# ERN_Main_4.net
KiCad netlist of a schematic drawn in Altium Designer
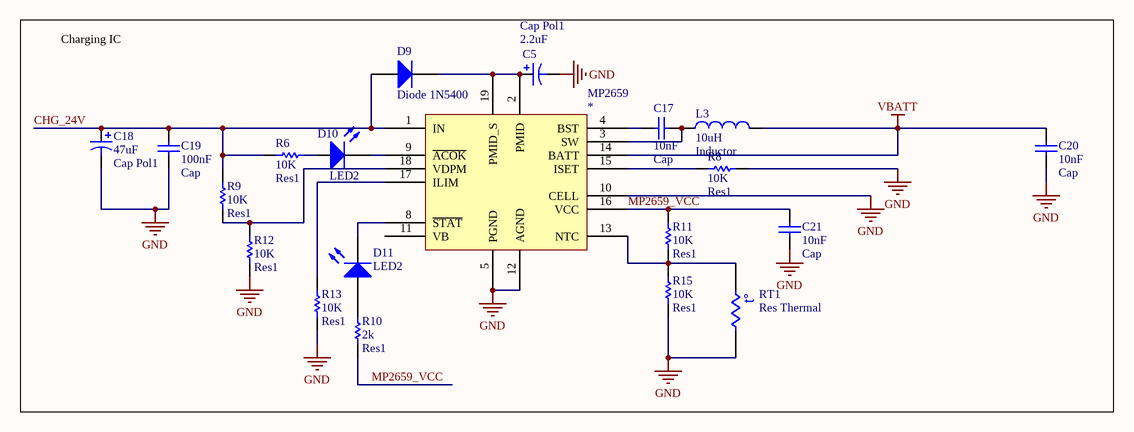
[diagram p0: ERN_Main_4.SchDoc]

(export (version "E")
  (design (tool "Eeschema 10.0.6"))
  (components
    (comp (ref "*")
      (value "MP2659")
      (description "3S-6S Standalone Switching Charger")
      (libsource (lib "ERN") (part "MP2659"))
    )
    (comp (ref "C5")
      (value "Cap Pol1")
      (footprint "RB7.6-15")
      (description "Polarized Capacitor (Radial)")
      (fields (field (name "ALTIUM_VALUE") "2.2uF") (field (name "PUBLISHER") "Altium Limited"))
      (libsource (lib "Miscellaneous Devices") (part "Cap Pol1"))
    )
    (comp (ref "C17")
      (value "Cap")
      (footprint "RAD-0.3")
      (description "Capacitor")
      (fields (field (name "ALTIUM_VALUE") "10nF") (field (name "PUBLISHER") "Altium Limited"))
      (libsource (lib "Miscellaneous Devices") (part "Cap"))
    )
    (comp (ref "C18")
      (value "Cap Pol1")
      (footprint "RB7.6-15")
      (description "Polarized Capacitor (Radial)")
      (fields (field (name "ALTIUM_VALUE") "47uF") (field (name "PUBLISHER") "Altium Limited"))
      (libsource (lib "Miscellaneous Devices") (part "Cap Pol1"))
    )
    (comp (ref "C19")
      (value "Cap")
      (footprint "RAD-0.3")
      (description "Capacitor")
      (fields (field (name "ALTIUM_VALUE") "100nF") (field (name "PUBLISHER") "Altium Limited"))
      (libsource (lib "Miscellaneous Devices") (part "Cap"))
    )
    (comp (ref "C20")
      (value "Cap")
      (footprint "RAD-0.3")
      (description "Capacitor")
      (fields (field (name "ALTIUM_VALUE") "10nF") (field (name "PUBLISHER") "Altium Limited"))
      (libsource (lib "Miscellaneous Devices") (part "Cap"))
    )
    (comp (ref "C21")
      (value "Cap")
      (footprint "RAD-0.3")
      (description "Capacitor")
      (fields (field (name "ALTIUM_VALUE") "10nF") (field (name "PUBLISHER") "Altium Limited"))
      (libsource (lib "Miscellaneous Devices") (part "Cap"))
    )
    (comp (ref "D9")
      (value "Diode 1N5400")
      (footprint "DO-201AD")
      (description "3 Amp General Purpose Rectifier")
      (fields (field (name "PUBLISHER") "Altium Limited"))
      (libsource (lib "Miscellaneous Devices") (part "Diode 1N5400"))
    )
    (comp (ref "D10")
      (value "LED2")
      (footprint "3.2X1.6X1.1")
      (description "Typical RED, GREEN, YELLOW, AMBER GaAs LED")
      (fields (field (name "PUBLISHER") "Altium Limited"))
      (libsource (lib "Miscellaneous Devices") (part "LED2"))
    )
    (comp (ref "D11")
      (value "LED2")
      (footprint "3.2X1.6X1.1")
      (description "Typical RED, GREEN, YELLOW, AMBER GaAs LED")
      (fields (field (name "PUBLISHER") "Altium Limited"))
      (libsource (lib "Miscellaneous Devices") (part "LED2"))
    )
    (comp (ref "L3")
      (value "Inductor")
      (footprint "0402-A")
      (fields (field (name "ALTIUM_VALUE") "10uH") (field (name "PUBLISHER") "Altium Limited"))
      (libsource (lib "Miscellaneous Devices") (part "Inductor"))
    )
    (comp (ref "R6")
      (value "Res1")
      (footprint "AXIAL-0.3")
      (description "Resistor")
      (fields (field (name "ALTIUM_VALUE") "10K") (field (name "PUBLISHER") "Altium Limited"))
      (libsource (lib "Miscellaneous Devices") (part "Res1"))
    )
    (comp (ref "R8")
      (value "Res1")
      (footprint "AXIAL-0.3")
      (description "Resistor")
      (fields (field (name "ALTIUM_VALUE") "10K") (field (name "PUBLISHER") "Altium Limited"))
      (libsource (lib "Miscellaneous Devices") (part "Res1"))
    )
    (comp (ref "R9")
      (value "Res1")
      (footprint "AXIAL-0.3")
      (description "Resistor")
      (fields (field (name "ALTIUM_VALUE") "10K") (field (name "PUBLISHER") "Altium Limited"))
      (libsource (lib "Miscellaneous Devices") (part "Res1"))
    )
    (comp (ref "R10")
      (value "Res1")
      (footprint "AXIAL-0.3")
      (description "Resistor")
      (fields (field (name "ALTIUM_VALUE") "2k") (field (name "PUBLISHER") "Altium Limited"))
      (libsource (lib "Miscellaneous Devices") (part "Res1"))
    )
    (comp (ref "R11")
      (value "Res1")
      (footprint "AXIAL-0.3")
      (description "Resistor")
      (fields (field (name "ALTIUM_VALUE") "10K") (field (name "PUBLISHER") "Altium Limited"))
      (libsource (lib "Miscellaneous Devices") (part "Res1"))
    )
    (comp (ref "R12")
      (value "Res1")
      (footprint "AXIAL-0.3")
      (description "Resistor")
      (fields (field (name "ALTIUM_VALUE") "10K") (field (name "PUBLISHER") "Altium Limited"))
      (libsource (lib "Miscellaneous Devices") (part "Res1"))
    )
    (comp (ref "R13")
      (value "Res1")
      (footprint "AXIAL-0.3")
      (description "Resistor")
      (fields (field (name "ALTIUM_VALUE") "10K") (field (name "PUBLISHER") "Altium Limited"))
      (libsource (lib "Miscellaneous Devices") (part "Res1"))
    )
    (comp (ref "R15")
      (value "Res1")
      (footprint "AXIAL-0.3")
      (description "Resistor")
      (fields (field (name "ALTIUM_VALUE") "10K") (field (name "PUBLISHER") "Altium Limited"))
      (libsource (lib "Miscellaneous Devices") (part "Res1"))
    )
    (comp (ref "RT1")
      (value "Res Thermal")
      (footprint "6-0805_N")
      (description "Thermistor")
      (fields (field (name "PUBLISHER") "Altium Limited"))
      (libsource (lib "Miscellaneous Devices") (part "Res Thermal"))
    )
  )
  (nets
    (net (code "1") (name "/CHG_24V") (class "Default")
      (node (ref "*") (pin "1") (pinfunction "IN_1") (pintype "passive"))
      (node (ref "C18") (pin "1") (pinfunction "1_1") (pintype "passive"))
      (node (ref "C19") (pin "2") (pinfunction "2_2") (pintype "passive"))
      (node (ref "D9") (pin "1") (pinfunction "A_1") (pintype "passive"))
      (node (ref "R6") (pin "2") (pinfunction "2_2") (pintype "passive"))
      (node (ref "R9") (pin "1") (pinfunction "1_1") (pintype "passive"))
    )
    (net (code "2") (name "/MP2659_VCC") (class "Default")
      (node (ref "*") (pin "16") (pinfunction "VCC_16") (pintype "passive"))
      (node (ref "C21") (pin "1") (pinfunction "1_1") (pintype "passive"))
      (node (ref "R10") (pin "2") (pinfunction "2_2") (pintype "passive"))
      (node (ref "R11") (pin "2") (pinfunction "2_2") (pintype "passive"))
    )
    (net (code "3") (name "GND") (class "Default")
      (node (ref "*") (pin "10") (pinfunction "CELL_10") (pintype "passive"))
      (node (ref "*") (pin "12") (pinfunction "AGND_12") (pintype "passive"))
      (node (ref "*") (pin "5") (pinfunction "PGND_5") (pintype "passive"))
      (node (ref "C18") (pin "2") (pinfunction "2_2") (pintype "passive"))
      (node (ref "C19") (pin "1") (pinfunction "1_1") (pintype "passive"))
      (node (ref "C20") (pin "2") (pinfunction "2_2") (pintype "passive"))
      (node (ref "C21") (pin "2") (pinfunction "2_2") (pintype "passive"))
      (node (ref "C5") (pin "2") (pinfunction "2_2") (pintype "passive"))
      (node (ref "R12") (pin "2") (pinfunction "2_2") (pintype "passive"))
      (node (ref "R13") (pin "2") (pinfunction "2_2") (pintype "passive"))
      (node (ref "R15") (pin "1") (pinfunction "1_1") (pintype "passive"))
      (node (ref "R8") (pin "2") (pinfunction "2_2") (pintype "passive"))
      (node (ref "RT1") (pin "2") (pinfunction "2_2") (pintype "passive"))
    )
    (net (code "4") (name "Net-(*-BST)") (class "Default")
      (node (ref "*") (pin "4") (pinfunction "BST_4") (pintype "passive"))
      (node (ref "C17") (pin "2") (pinfunction "2_2") (pintype "passive"))
    )
    (net (code "5") (name "Net-(*-ILIM)") (class "Default")
      (node (ref "*") (pin "17") (pinfunction "ILIM_17") (pintype "passive"))
      (node (ref "R13") (pin "1") (pinfunction "1_1") (pintype "passive"))
    )
    (net (code "6") (name "Net-(*-ISET)") (class "Default")
      (node (ref "*") (pin "15") (pinfunction "ISET_15") (pintype "passive"))
      (node (ref "R8") (pin "1") (pinfunction "1_1") (pintype "passive"))
    )
    (net (code "7") (name "Net-(*-NTC)") (class "Default")
      (node (ref "*") (pin "13") (pinfunction "NTC_13") (pintype "passive"))
      (node (ref "R11") (pin "1") (pinfunction "1_1") (pintype "passive"))
      (node (ref "R15") (pin "2") (pinfunction "2_2") (pintype "passive"))
      (node (ref "RT1") (pin "1") (pinfunction "1_1") (pintype "passive"))
    )
    (net (code "8") (name "Net-(*-PMID)") (class "Default")
      (node (ref "*") (pin "19") (pinfunction "PMID_S_19") (pintype "passive"))
      (node (ref "*") (pin "2") (pinfunction "PMID_2") (pintype "passive"))
      (node (ref "C5") (pin "1") (pinfunction "1_1") (pintype "passive"))
      (node (ref "D9") (pin "2") (pinfunction "K_2") (pintype "passive"))
    )
    (net (code "9") (name "Net-(*-SW)") (class "Default")
      (node (ref "*") (pin "3") (pinfunction "SW_3") (pintype "passive"))
      (node (ref "C17") (pin "1") (pinfunction "1_1") (pintype "passive"))
      (node (ref "L3") (pin "1") (pinfunction "1_1") (pintype "passive"))
    )
    (net (code "10") (name "Net-(*-VDPM)") (class "Default")
      (node (ref "*") (pin "18") (pinfunction "VDPM_18") (pintype "passive"))
      (node (ref "R12") (pin "1") (pinfunction "1_1") (pintype "passive"))
      (node (ref "R9") (pin "2") (pinfunction "2_2") (pintype "passive"))
    )
    (net (code "11") (name "Net-(*-~{ACOK})") (class "Default")
      (node (ref "*") (pin "9") (pinfunction "~{ACOK}_9") (pintype "passive"))
      (node (ref "D10") (pin "2") (pinfunction "K_2") (pintype "passive"))
    )
    (net (code "12") (name "Net-(*-~{STAT})") (class "Default")
      (node (ref "*") (pin "8") (pinfunction "~{STAT}_8") (pintype "passive"))
      (node (ref "D11") (pin "2") (pinfunction "K_2") (pintype "passive"))
    )
    (net (code "13") (name "Net-(D10-A)") (class "Default")
      (node (ref "D10") (pin "1") (pinfunction "A_1") (pintype "passive"))
      (node (ref "R6") (pin "1") (pinfunction "1_1") (pintype "passive"))
    )
    (net (code "14") (name "Net-(D11-A)") (class "Default")
      (node (ref "D11") (pin "1") (pinfunction "A_1") (pintype "passive"))
      (node (ref "R10") (pin "1") (pinfunction "1_1") (pintype "passive"))
    )
    (net (code "15") (name "VBATT") (class "Default")
      (node (ref "*") (pin "14") (pinfunction "BATT_14") (pintype "passive"))
      (node (ref "C20") (pin "1") (pinfunction "1_1") (pintype "passive"))
      (node (ref "L3") (pin "2") (pinfunction "2_2") (pintype "passive"))
    )
    (net (code "16") (name "unconnected-(*-VB-Pad11)") (class "Default")
      (node (ref "*") (pin "11") (pinfunction "VB_11") (pintype "passive"))
    )
  )
)
